# MCU.net
KiCad netlist of a schematic drawn in Altium Designer
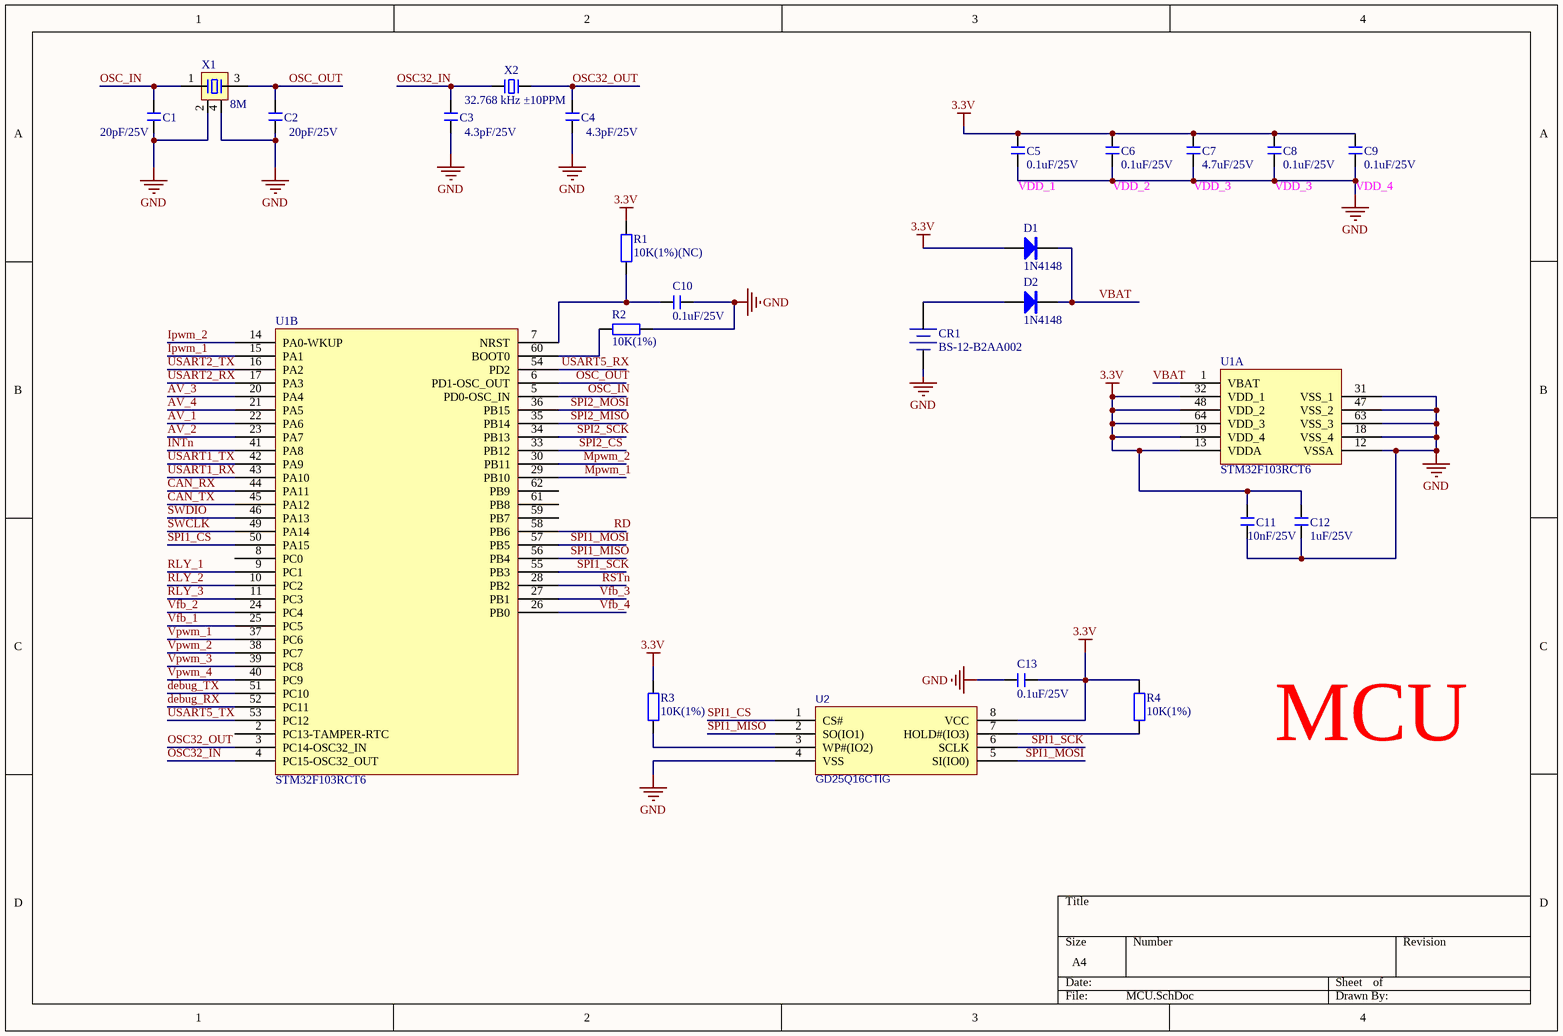
[diagram p0: MCU.SchDoc]

(export (version "E")
  (design (tool "Eeschema 10.0.6"))
  (components
    (comp (ref "C1")
      (value "20pF/25V")
      (footprint "C 0603_L")
      (description "无极性贴片电容")
      (fields (field (name "版权归属") "源创客"))
      (libsource (lib "电阻-电容-电感") (part "C"))
    )
    (comp (ref "C2")
      (value "20pF/25V")
      (footprint "C 0603_L")
      (description "无极性贴片电容")
      (fields (field (name "版权归属") "源创客"))
      (libsource (lib "电阻-电容-电感") (part "C"))
    )
    (comp (ref "C3")
      (value "4.3pF/25V")
      (footprint "C 0603_L")
      (description "无极性贴片电容")
      (fields (field (name "版权归属") "源创客"))
      (libsource (lib "电阻-电容-电感") (part "C"))
    )
    (comp (ref "C4")
      (value "4.3pF/25V")
      (footprint "C 0603_L")
      (description "无极性贴片电容")
      (fields (field (name "版权归属") "源创客"))
      (libsource (lib "电阻-电容-电感") (part "C"))
    )
    (comp (ref "C5")
      (value "0.1uF/25V")
      (footprint "C 0603_L")
      (description "无极性贴片电容")
      (fields (field (name "版权归属") "源创客"))
      (libsource (lib "电阻-电容-电感") (part "C"))
    )
    (comp (ref "C6")
      (value "0.1uF/25V")
      (footprint "C 0603_L")
      (description "无极性贴片电容")
      (fields (field (name "版权归属") "源创客"))
      (libsource (lib "电阻-电容-电感") (part "C"))
    )
    (comp (ref "C7")
      (value "4.7uF/25V")
      (footprint "C 0603_L")
      (description "无极性贴片电容")
      (fields (field (name "版权归属") "源创客"))
      (libsource (lib "电阻-电容-电感") (part "C"))
    )
    (comp (ref "C8")
      (value "0.1uF/25V")
      (footprint "C 0603_L")
      (description "无极性贴片电容")
      (fields (field (name "版权归属") "源创客"))
      (libsource (lib "电阻-电容-电感") (part "C"))
    )
    (comp (ref "C9")
      (value "0.1uF/25V")
      (footprint "C 0603_L")
      (description "无极性贴片电容")
      (fields (field (name "版权归属") "源创客"))
      (libsource (lib "电阻-电容-电感") (part "C"))
    )
    (comp (ref "C10")
      (value "0.1uF/25V")
      (footprint "C 0603_L")
      (description "无极性贴片电容")
      (fields (field (name "版权归属") "源创客"))
      (libsource (lib "电阻-电容-电感") (part "C"))
    )
    (comp (ref "C11")
      (value "10nF/25V")
      (footprint "C 0603_L")
      (description "无极性贴片电容")
      (fields (field (name "版权归属") "源创客"))
      (libsource (lib "电阻-电容-电感") (part "C"))
    )
    (comp (ref "C12")
      (value "1uF/25V")
      (footprint "C 0603_L")
      (description "无极性贴片电容")
      (fields (field (name "版权归属") "源创客"))
      (libsource (lib "电阻-电容-电感") (part "C"))
    )
    (comp (ref "C13")
      (value "0.1uF/25V")
      (footprint "C 0603_L")
      (description "无极性贴片电容")
      (fields (field (name "版权归属") "源创客"))
      (libsource (lib "电阻-电容-电感") (part "C"))
    )
    (comp (ref "CR1")
      (value "BS-12-B2AA002")
      (footprint "CR1220_B")
      (description "MYOUNG(美阳) 电池底座 适用电池:CR1220")
      (fields (field (name "版权归属") "源创客"))
      (libsource (lib "蜂鸣器-电池座-测试点") (part "CR-3V"))
    )
    (comp (ref "D1")
      (value "1N4148")
      (footprint "SOD-323")
      (description "高速开关二极管")
      (fields (field (name "版权归属") "源创客"))
      (libsource (lib "二极管-整流桥") (part "1N4148"))
    )
    (comp (ref "D2")
      (value "1N4148")
      (footprint "SOD-323")
      (description "高速开关二极管")
      (fields (field (name "版权归属") "源创客"))
      (libsource (lib "二极管-整流桥") (part "1N4148"))
    )
    (comp (ref "R1")
      (value "10K(1%)(NC)")
      (footprint "R 0603_L")
      (description "贴片电阻")
      (fields (field (name "版权归属") "源创客"))
      (libsource (lib "电阻-电容-电感") (part "R"))
    )
    (comp (ref "R2")
      (value "10K(1%)")
      (footprint "R 0603_L")
      (description "贴片电阻")
      (fields (field (name "版权归属") "源创客"))
      (libsource (lib "电阻-电容-电感") (part "R"))
    )
    (comp (ref "R3")
      (value "10K(1%)")
      (footprint "R 0603_L")
      (description "贴片电阻")
      (fields (field (name "版权归属") "源创客"))
      (libsource (lib "电阻-电容-电感") (part "R"))
    )
    (comp (ref "R4")
      (value "10K(1%)")
      (footprint "R 0603_L")
      (description "贴片电阻")
      (fields (field (name "版权归属") "源创客"))
      (libsource (lib "电阻-电容-电感") (part "R"))
    )
    (comp (ref "U1")
      (value "STM32F103RCT6")
      (footprint "LQFP64 10x10_N")
      (libsource (lib "MICB") (part "STM32F103RCT6"))
    )
    (comp (ref "U2")
      (value "GD25Q16CTIG")
      (footprint "SOP-8")
      (description "spi flash")
      (fields
        (field (name "BOM_SUPPLIER PART") "C558851")
        (field (name "BOM_MANUFACTURER PART") "XT25F32BSOIGU-S")
        (field (name "CONTRIBUTOR") "LCSC")
      )
      (libsource (lib "MICB") (part "GD25Q16CTIG"))
    )
    (comp (ref "X1")
      (value "8M")
      (footprint "OSC 3225-4P")
      (description "4脚无源晶振")
      (fields (field (name "版权归属") "源创客"))
      (libsource (lib "保险丝-晶振") (part "XTAL-4P"))
    )
    (comp (ref "X2")
      (value "32.768 kHz ±10PPM")
      (footprint "OSC 3215-2P")
      (description "2脚无源脚晶振 型号Q13FC13500005")
      (fields (field (name "版权归属") "源创客"))
      (libsource (lib "保险丝-晶振") (part "XTAL-2P"))
    )
  )
  (nets
    (net (code "1") (name "/AV_1") (class "Default")
      (node (ref "U1") (pin "22") (pinfunction "PA6_22") (pintype "passive"))
    )
    (net (code "2") (name "/AV_2") (class "Default")
      (node (ref "U1") (pin "23") (pinfunction "PA7_23") (pintype "passive"))
    )
    (net (code "3") (name "/AV_3") (class "Default")
      (node (ref "U1") (pin "20") (pinfunction "PA4_20") (pintype "passive"))
    )
    (net (code "4") (name "/AV_4") (class "Default")
      (node (ref "U1") (pin "21") (pinfunction "PA5_21") (pintype "passive"))
    )
    (net (code "5") (name "/CAN_RX") (class "Default")
      (node (ref "U1") (pin "44") (pinfunction "PA11_44") (pintype "passive"))
    )
    (net (code "6") (name "/CAN_TX") (class "Default")
      (node (ref "U1") (pin "45") (pinfunction "PA12_45") (pintype "passive"))
    )
    (net (code "7") (name "/INTn") (class "Default")
      (node (ref "U1") (pin "41") (pinfunction "PA8_41") (pintype "passive"))
    )
    (net (code "8") (name "/Ipwm_1") (class "Default")
      (node (ref "U1") (pin "15") (pinfunction "PA1_15") (pintype "passive"))
    )
    (net (code "9") (name "/Ipwm_2") (class "Default")
      (node (ref "U1") (pin "14") (pinfunction "PA0-WKUP_14") (pintype "passive"))
    )
    (net (code "10") (name "/Mpwm_1") (class "Default")
      (node (ref "U1") (pin "29") (pinfunction "PB10_29") (pintype "passive"))
    )
    (net (code "11") (name "/Mpwm_2") (class "Default")
      (node (ref "U1") (pin "30") (pinfunction "PB11_30") (pintype "passive"))
    )
    (net (code "12") (name "/OSC32_IN") (class "Default")
      (node (ref "C3") (pin "1") (pinfunction "1_1") (pintype "passive"))
      (node (ref "U1") (pin "4") (pinfunction "PC15-OSC32_OUT_4") (pintype "passive"))
      (node (ref "X2") (pin "1") (pinfunction "1_1") (pintype "passive"))
    )
    (net (code "13") (name "/OSC32_OUT") (class "Default")
      (node (ref "C4") (pin "1") (pinfunction "1_1") (pintype "passive"))
      (node (ref "U1") (pin "3") (pinfunction "PC14-OSC32_IN_3") (pintype "passive"))
      (node (ref "X2") (pin "2") (pinfunction "2_2") (pintype "passive"))
    )
    (net (code "14") (name "/OSC_IN") (class "Default")
      (node (ref "C1") (pin "1") (pinfunction "1_1") (pintype "passive"))
      (node (ref "U1") (pin "5") (pinfunction "PD0-OSC_IN_5") (pintype "passive"))
      (node (ref "X1") (pin "1") (pinfunction "1_1") (pintype "passive"))
    )
    (net (code "15") (name "/OSC_OUT") (class "Default")
      (node (ref "C2") (pin "1") (pinfunction "1_1") (pintype "passive"))
      (node (ref "U1") (pin "6") (pinfunction "PD1-OSC_OUT_6") (pintype "passive"))
      (node (ref "X1") (pin "3") (pinfunction "3_3") (pintype "passive"))
    )
    (net (code "16") (name "/RD") (class "Default")
      (node (ref "U1") (pin "58") (pinfunction "PB6_58") (pintype "passive"))
    )
    (net (code "17") (name "/RLY_1") (class "Default")
      (node (ref "U1") (pin "9") (pinfunction "PC1_9") (pintype "passive"))
    )
    (net (code "18") (name "/RLY_2") (class "Default")
      (node (ref "U1") (pin "10") (pinfunction "PC2_10") (pintype "passive"))
    )
    (net (code "19") (name "/RLY_3") (class "Default")
      (node (ref "U1") (pin "11") (pinfunction "PC3_11") (pintype "passive"))
    )
    (net (code "20") (name "/RSTn") (class "Default")
      (node (ref "U1") (pin "28") (pinfunction "PB2_28") (pintype "passive"))
    )
    (net (code "21") (name "/SPI1_CS") (class "Default")
      (node (ref "U1") (pin "50") (pinfunction "PA15_50") (pintype "passive"))
      (node (ref "U2") (pin "1") (pinfunction "CS#_1") (pintype "passive"))
    )
    (net (code "22") (name "/SPI1_MISO") (class "Default")
      (node (ref "U1") (pin "56") (pinfunction "PB4_56") (pintype "passive"))
      (node (ref "U2") (pin "2") (pinfunction "SO(IO1)_2") (pintype "passive"))
    )
    (net (code "23") (name "/SPI1_MOSI") (class "Default")
      (node (ref "U1") (pin "57") (pinfunction "PB5_57") (pintype "passive"))
      (node (ref "U2") (pin "5") (pinfunction "SI(IO0)_5") (pintype "passive"))
    )
    (net (code "24") (name "/SPI1_SCK") (class "Default")
      (node (ref "U1") (pin "55") (pinfunction "PB3_55") (pintype "passive"))
      (node (ref "U2") (pin "6") (pinfunction "SCLK_6") (pintype "passive"))
    )
    (net (code "25") (name "/SPI2_CS") (class "Default")
      (node (ref "U1") (pin "33") (pinfunction "PB12_33") (pintype "passive"))
    )
    (net (code "26") (name "/SPI2_MISO") (class "Default")
      (node (ref "U1") (pin "35") (pinfunction "PB14_35") (pintype "passive"))
    )
    (net (code "27") (name "/SPI2_MOSI") (class "Default")
      (node (ref "U1") (pin "36") (pinfunction "PB15_36") (pintype "passive"))
    )
    (net (code "28") (name "/SPI2_SCK") (class "Default")
      (node (ref "U1") (pin "34") (pinfunction "PB13_34") (pintype "passive"))
    )
    (net (code "29") (name "/SWCLK") (class "Default")
      (node (ref "U1") (pin "49") (pinfunction "PA14_49") (pintype "passive"))
    )
    (net (code "30") (name "/SWDIO") (class "Default")
      (node (ref "U1") (pin "46") (pinfunction "PA13_46") (pintype "passive"))
    )
    (net (code "31") (name "/USART1_RX") (class "Default")
      (node (ref "U1") (pin "43") (pinfunction "PA10_43") (pintype "passive"))
    )
    (net (code "32") (name "/USART1_TX") (class "Default")
      (node (ref "U1") (pin "42") (pinfunction "PA9_42") (pintype "passive"))
    )
    (net (code "33") (name "/USART2_RX") (class "Default")
      (node (ref "U1") (pin "17") (pinfunction "PA3_17") (pintype "passive"))
    )
    (net (code "34") (name "/USART2_TX") (class "Default")
      (node (ref "U1") (pin "16") (pinfunction "PA2_16") (pintype "passive"))
    )
    (net (code "35") (name "/USART5_RX") (class "Default")
      (node (ref "U1") (pin "54") (pinfunction "PD2_54") (pintype "passive"))
    )
    (net (code "36") (name "/USART5_TX") (class "Default")
      (node (ref "U1") (pin "53") (pinfunction "PC12_53") (pintype "passive"))
    )
    (net (code "37") (name "/VBAT") (class "Default")
      (node (ref "D1") (pin "2") (pinfunction "K_2") (pintype "passive"))
      (node (ref "D2") (pin "2") (pinfunction "K_2") (pintype "passive"))
      (node (ref "U1") (pin "1") (pinfunction "VBAT_1") (pintype "passive"))
    )
    (net (code "38") (name "/Vfb_1") (class "Default")
      (node (ref "U1") (pin "25") (pinfunction "PC5_25") (pintype "passive"))
    )
    (net (code "39") (name "/Vfb_2") (class "Default")
      (node (ref "U1") (pin "24") (pinfunction "PC4_24") (pintype "passive"))
    )
    (net (code "40") (name "/Vfb_3") (class "Default")
      (node (ref "U1") (pin "27") (pinfunction "PB1_27") (pintype "passive"))
    )
    (net (code "41") (name "/Vfb_4") (class "Default")
      (node (ref "U1") (pin "26") (pinfunction "PB0_26") (pintype "passive"))
    )
    (net (code "42") (name "/Vpwm_1") (class "Default")
      (node (ref "U1") (pin "37") (pinfunction "PC6_37") (pintype "passive"))
    )
    (net (code "43") (name "/Vpwm_2") (class "Default")
      (node (ref "U1") (pin "38") (pinfunction "PC7_38") (pintype "passive"))
    )
    (net (code "44") (name "/Vpwm_3") (class "Default")
      (node (ref "U1") (pin "39") (pinfunction "PC8_39") (pintype "passive"))
    )
    (net (code "45") (name "/Vpwm_4") (class "Default")
      (node (ref "U1") (pin "40") (pinfunction "PC9_40") (pintype "passive"))
    )
    (net (code "46") (name "/debug_RX") (class "Default")
      (node (ref "U1") (pin "52") (pinfunction "PC11_52") (pintype "passive"))
    )
    (net (code "47") (name "/debug_TX") (class "Default")
      (node (ref "U1") (pin "51") (pinfunction "PC10_51") (pintype "passive"))
    )
    (net (code "48") (name "3.3V") (class "Default")
      (node (ref "C11") (pin "1") (pinfunction "1_1") (pintype "passive"))
      (node (ref "C12") (pin "1") (pinfunction "1_1") (pintype "passive"))
      (node (ref "C13") (pin "2") (pinfunction "2_2") (pintype "passive"))
      (node (ref "C5") (pin "2") (pinfunction "2_2") (pintype "passive"))
      (node (ref "C6") (pin "2") (pinfunction "2_2") (pintype "passive"))
      (node (ref "C7") (pin "2") (pinfunction "2_2") (pintype "passive"))
      (node (ref "C8") (pin "2") (pinfunction "2_2") (pintype "passive"))
      (node (ref "C9") (pin "2") (pinfunction "2_2") (pintype "passive"))
      (node (ref "D1") (pin "1") (pinfunction "A_1") (pintype "passive"))
      (node (ref "R1") (pin "2") (pinfunction "2_2") (pintype "passive"))
      (node (ref "R3") (pin "1") (pinfunction "1_1") (pintype "passive"))
      (node (ref "R4") (pin "1") (pinfunction "1_1") (pintype "passive"))
      (node (ref "U1") (pin "13") (pinfunction "VDDA_13") (pintype "passive"))
      (node (ref "U1") (pin "19") (pinfunction "VDD_4_19") (pintype "passive"))
      (node (ref "U1") (pin "32") (pinfunction "VDD_1_32") (pintype "passive"))
      (node (ref "U1") (pin "48") (pinfunction "VDD_2_48") (pintype "passive"))
      (node (ref "U1") (pin "64") (pinfunction "VDD_3_64") (pintype "passive"))
      (node (ref "U2") (pin "8") (pinfunction "VCC_8") (pintype "passive"))
    )
    (net (code "49") (name "GND") (class "Default")
      (node (ref "C1") (pin "2") (pinfunction "2_2") (pintype "passive"))
      (node (ref "C10") (pin "1") (pinfunction "1_1") (pintype "passive"))
      (node (ref "C11") (pin "2") (pinfunction "2_2") (pintype "passive"))
      (node (ref "C12") (pin "2") (pinfunction "2_2") (pintype "passive"))
      (node (ref "C13") (pin "1") (pinfunction "1_1") (pintype "passive"))
      (node (ref "C2") (pin "2") (pinfunction "2_2") (pintype "passive"))
      (node (ref "C3") (pin "2") (pinfunction "2_2") (pintype "passive"))
      (node (ref "C4") (pin "2") (pinfunction "2_2") (pintype "passive"))
      (node (ref "C5") (pin "1") (pinfunction "1_1") (pintype "passive"))
      (node (ref "C6") (pin "1") (pinfunction "1_1") (pintype "passive"))
      (node (ref "C7") (pin "1") (pinfunction "1_1") (pintype "passive"))
      (node (ref "C8") (pin "1") (pinfunction "1_1") (pintype "passive"))
      (node (ref "C9") (pin "1") (pinfunction "1_1") (pintype "passive"))
      (node (ref "CR1") (pin "2") (pinfunction "DC-_2") (pintype "passive"))
      (node (ref "R2") (pin "1") (pinfunction "1_1") (pintype "passive"))
      (node (ref "U1") (pin "12") (pinfunction "VSSA_12") (pintype "passive"))
      (node (ref "U1") (pin "18") (pinfunction "VSS_4_18") (pintype "passive"))
      (node (ref "U1") (pin "31") (pinfunction "VSS_1_31") (pintype "passive"))
      (node (ref "U1") (pin "47") (pinfunction "VSS_2_47") (pintype "passive"))
      (node (ref "U1") (pin "63") (pinfunction "VSS_3_63") (pintype "passive"))
      (node (ref "U2") (pin "4") (pinfunction "VSS_4") (pintype "passive"))
      (node (ref "X1") (pin "2") (pinfunction "2_2") (pintype "passive"))
      (node (ref "X1") (pin "4") (pinfunction "4_4") (pintype "passive"))
    )
    (net (code "50") (name "Net-(CR1-DC+)") (class "Default")
      (node (ref "CR1") (pin "1") (pinfunction "DC+_1") (pintype "passive"))
      (node (ref "D2") (pin "1") (pinfunction "A_1") (pintype "passive"))
    )
    (net (code "51") (name "Net-(U1B-BOOT0)") (class "Default")
      (node (ref "R2") (pin "2") (pinfunction "2_2") (pintype "passive"))
      (node (ref "U1") (pin "60") (pinfunction "BOOT0_60") (pintype "passive"))
    )
    (net (code "52") (name "Net-(U1B-NRST)") (class "Default")
      (node (ref "C10") (pin "2") (pinfunction "2_2") (pintype "passive"))
      (node (ref "R1") (pin "1") (pinfunction "1_1") (pintype "passive"))
      (node (ref "U1") (pin "7") (pinfunction "NRST_7") (pintype "passive"))
    )
    (net (code "53") (name "Net-(U2-HOLD#(IO3))") (class "Default")
      (node (ref "R4") (pin "2") (pinfunction "2_2") (pintype "passive"))
      (node (ref "U2") (pin "7") (pinfunction "HOLD#(IO3)_7") (pintype "passive"))
    )
    (net (code "54") (name "Net-(U2-WP#(IO2))") (class "Default")
      (node (ref "R3") (pin "2") (pinfunction "2_2") (pintype "passive"))
      (node (ref "U2") (pin "3") (pinfunction "WP#(IO2)_3") (pintype "passive"))
    )
    (net (code "55") (name "unconnected-(U1B-PB7-Pad59)") (class "Default")
      (node (ref "U1") (pin "59") (pinfunction "PB7_59") (pintype "passive"))
    )
    (net (code "56") (name "unconnected-(U1B-PB8-Pad61)") (class "Default")
      (node (ref "U1") (pin "61") (pinfunction "PB8_61") (pintype "passive"))
    )
    (net (code "57") (name "unconnected-(U1B-PB9-Pad62)") (class "Default")
      (node (ref "U1") (pin "62") (pinfunction "PB9_62") (pintype "passive"))
    )
    (net (code "58") (name "unconnected-(U1B-PC0-Pad8)") (class "Default")
      (node (ref "U1") (pin "8") (pinfunction "PC0_8") (pintype "passive"))
    )
    (net (code "59") (name "unconnected-(U1B-PC13-TAMPER-RTC-Pad2)") (class "Default")
      (node (ref "U1") (pin "2") (pinfunction "PC13-TAMPER-RTC_2") (pintype "passive"))
    )
  )
)
